# CYAN_AMP_2.net
KiCad netlist of a schematic drawn in Altium Designer
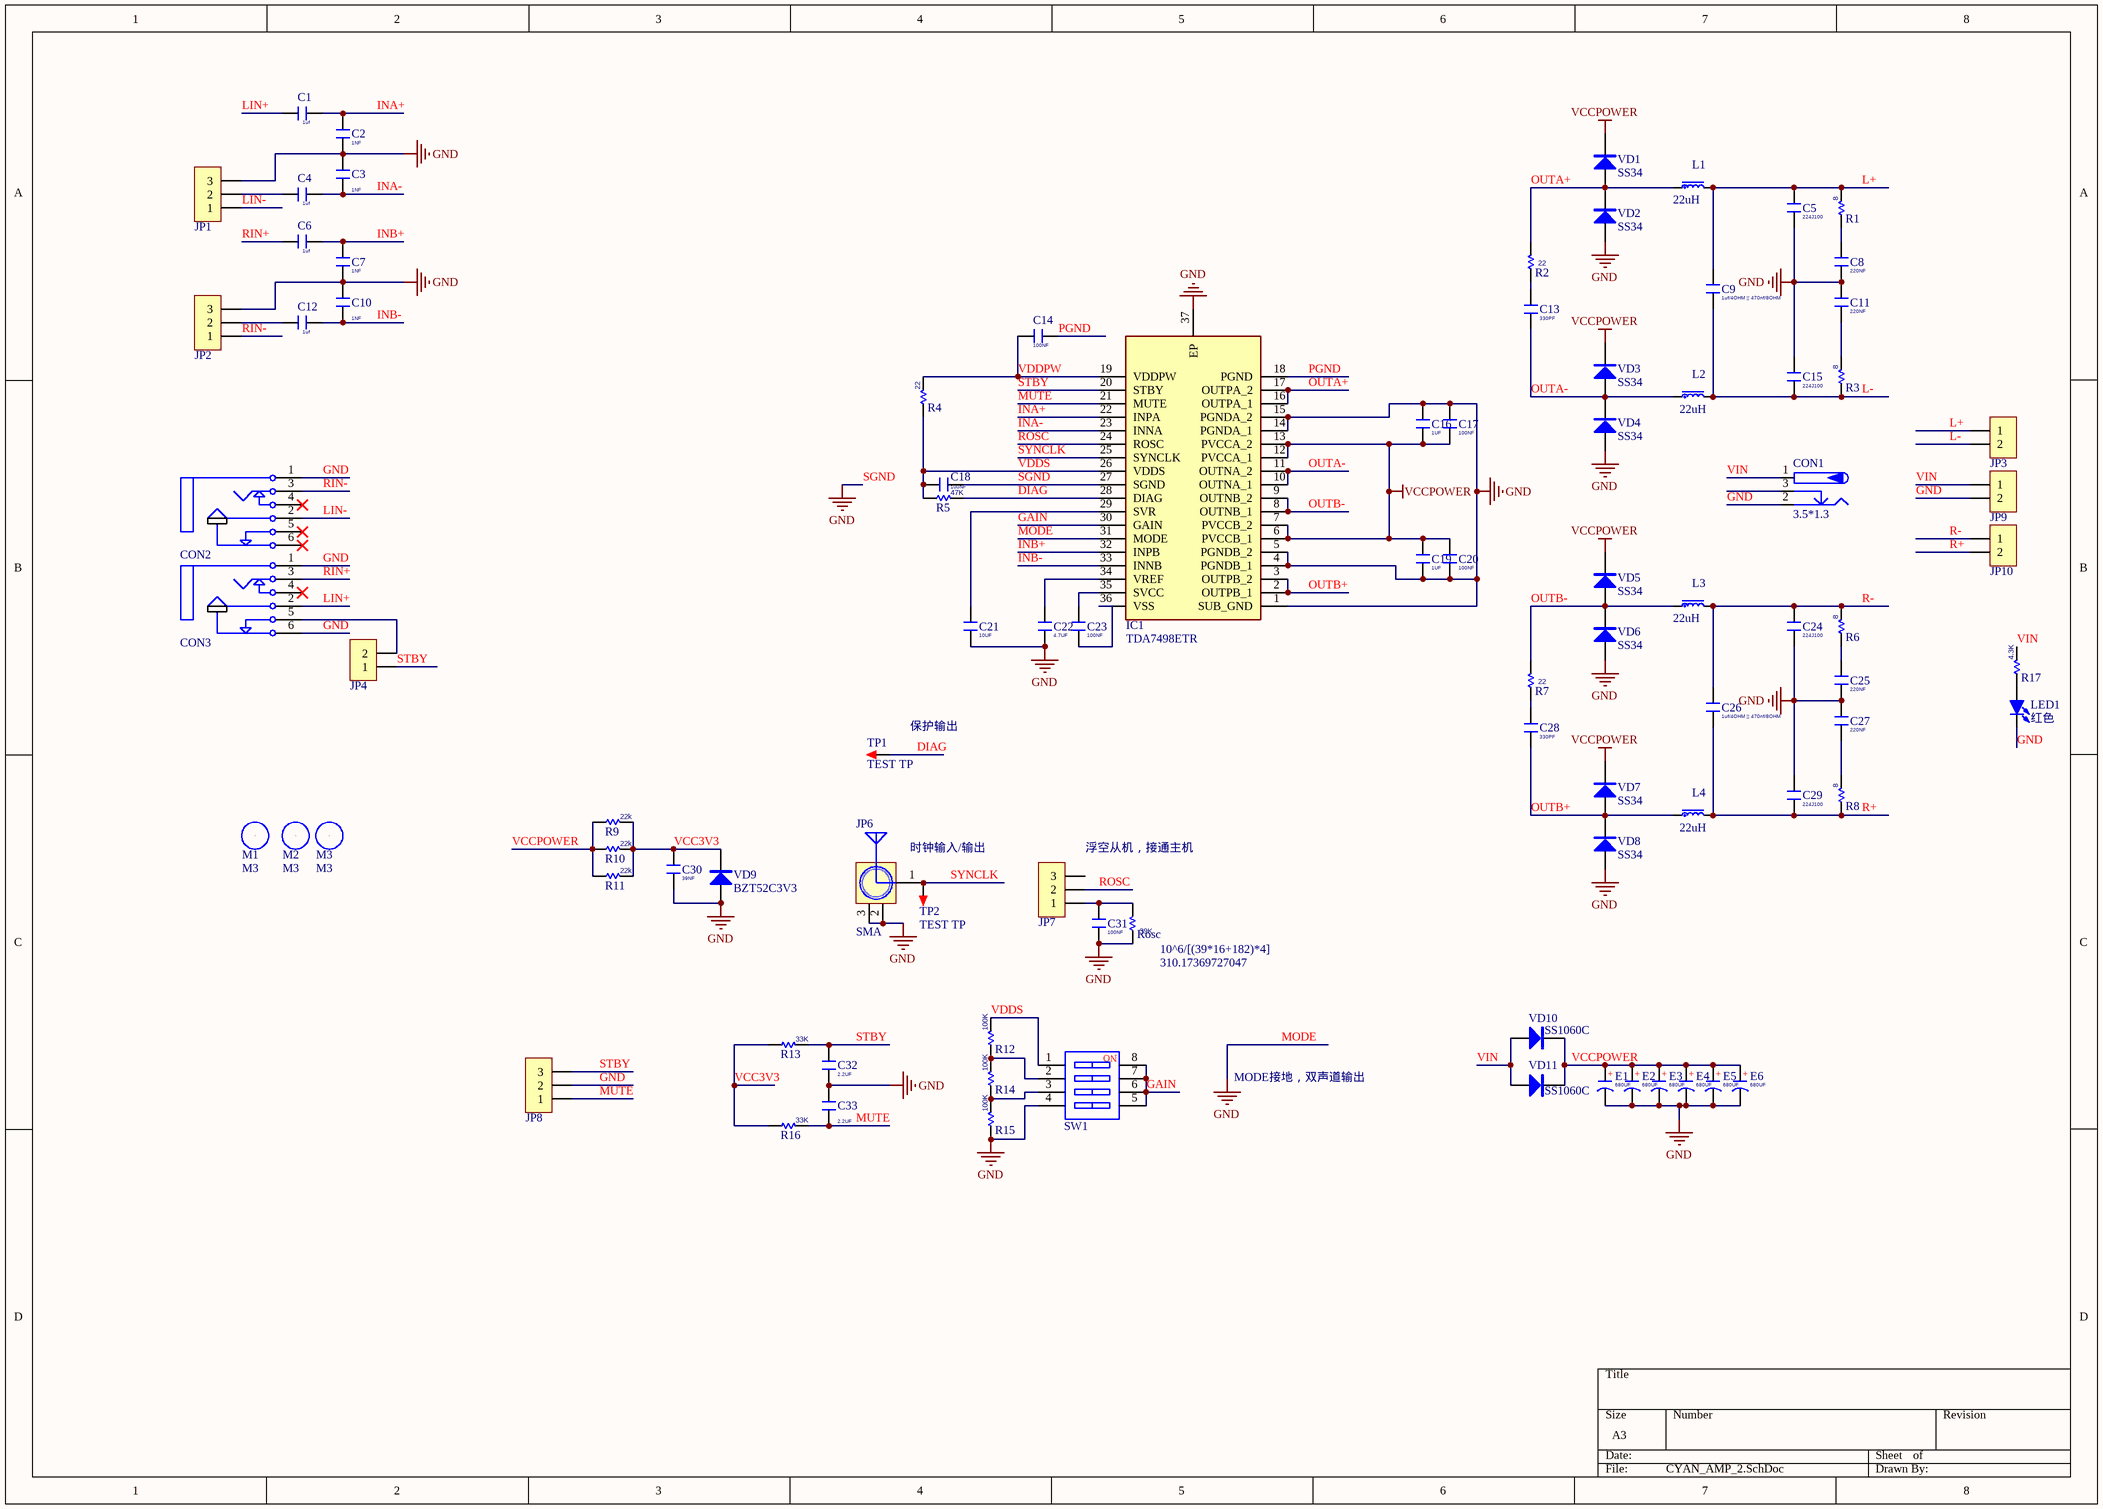
[diagram p0: CYAN_AMP_2.SchDoc]

(export (version "E")
  (design (tool "Eeschema 10.0.6"))
  (components
    (comp (ref "C1")
      (value "1uf")
      (footprint "CBB-T 5*10*5.4")
      (description "CBB电容")
      (fields (field (name "VOLTAGE") "10v"))
      (libsource (lib "电阻-电容-电感") (part "C-CBB"))
    )
    (comp (ref "C2")
      (value "1NF")
      (footprint "C 0805")
      (description "无极性贴片电容")
      (fields (field (name "VOLTAGE") "20V") (field (name "Comment") "C"))
      (libsource (lib "电阻-电容-电感") (part "C"))
    )
    (comp (ref "C3")
      (value "1NF")
      (footprint "C 0805")
      (description "无极性贴片电容")
      (fields (field (name "VOLTAGE") "20V") (field (name "Comment") "C"))
      (libsource (lib "电阻-电容-电感") (part "C"))
    )
    (comp (ref "C4")
      (value "1uf")
      (footprint "CBB-T 5*10*5.4")
      (description "CBB电容")
      (fields (field (name "VOLTAGE") "10v"))
      (libsource (lib "电阻-电容-电感") (part "C-CBB"))
    )
    (comp (ref "C5")
      (value "224J100")
      (footprint "CBB-T 5*7.5*3.5")
      (description "CBB电容")
      (fields (field (name "VOLTAGE") "10v"))
      (libsource (lib "电阻-电容-电感") (part "C-CBB"))
    )
    (comp (ref "C6")
      (value "1uf")
      (footprint "CBB-T 5*10*5.4")
      (description "CBB电容")
      (fields (field (name "VOLTAGE") "10v"))
      (libsource (lib "电阻-电容-电感") (part "C-CBB"))
    )
    (comp (ref "C7")
      (value "1NF")
      (footprint "C 0805")
      (description "无极性贴片电容")
      (fields (field (name "VOLTAGE") "20V") (field (name "Comment") "C"))
      (libsource (lib "电阻-电容-电感") (part "C"))
    )
    (comp (ref "C8")
      (value "220NF")
      (footprint "C 0805")
      (description "无极性贴片电容")
      (fields (field (name "VOLTAGE") "20V") (field (name "Comment") "C"))
      (libsource (lib "电阻-电容-电感") (part "C"))
    )
    (comp (ref "C9")
      (value "1uf/4OHM Ζ 470nf/8OHM")
      (footprint "CBB-T 5*10*5.4")
      (description "CBB电容")
      (fields (field (name "VOLTAGE") "10v"))
      (libsource (lib "电阻-电容-电感") (part "C-CBB"))
    )
    (comp (ref "C10")
      (value "1NF")
      (footprint "C 0805")
      (description "无极性贴片电容")
      (fields (field (name "VOLTAGE") "20V") (field (name "Comment") "C"))
      (libsource (lib "电阻-电容-电感") (part "C"))
    )
    (comp (ref "C11")
      (value "220NF")
      (footprint "C 0805")
      (description "无极性贴片电容")
      (fields (field (name "VOLTAGE") "20V") (field (name "Comment") "C"))
      (libsource (lib "电阻-电容-电感") (part "C"))
    )
    (comp (ref "C12")
      (value "1uf")
      (footprint "CBB-T 5*10*5.4")
      (description "CBB电容")
      (fields (field (name "VOLTAGE") "10v"))
      (libsource (lib "电阻-电容-电感") (part "C-CBB"))
    )
    (comp (ref "C13")
      (value "330PF")
      (footprint "C 0805")
      (description "无极性贴片电容")
      (fields (field (name "VOLTAGE") "20V") (field (name "Comment") "C"))
      (libsource (lib "电阻-电容-电感") (part "C"))
    )
    (comp (ref "C14")
      (value "100NF")
      (footprint "C 0805")
      (description "无极性贴片电容")
      (fields (field (name "VOLTAGE") "20V") (field (name "Comment") "C"))
      (libsource (lib "电阻-电容-电感") (part "C"))
    )
    (comp (ref "C15")
      (value "224J100")
      (footprint "CBB-T 5*7.5*3.5")
      (description "CBB电容")
      (fields (field (name "VOLTAGE") "10v"))
      (libsource (lib "电阻-电容-电感") (part "C-CBB"))
    )
    (comp (ref "C16")
      (value "1UF")
      (footprint "C 0805")
      (description "无极性贴片电容")
      (fields (field (name "VOLTAGE") "20V") (field (name "Comment") "C"))
      (libsource (lib "电阻-电容-电感") (part "C"))
    )
    (comp (ref "C17")
      (value "100NF")
      (footprint "C 0805")
      (description "无极性贴片电容")
      (fields (field (name "VOLTAGE") "20V") (field (name "Comment") "C"))
      (libsource (lib "电阻-电容-电感") (part "C"))
    )
    (comp (ref "C18")
      (value "100NF")
      (footprint "C 0805")
      (description "无极性贴片电容")
      (fields (field (name "VOLTAGE") "20V") (field (name "Comment") "C"))
      (libsource (lib "电阻-电容-电感") (part "C"))
    )
    (comp (ref "C19")
      (value "1UF")
      (footprint "C 0805")
      (description "无极性贴片电容")
      (fields (field (name "VOLTAGE") "20V") (field (name "Comment") "C"))
      (libsource (lib "电阻-电容-电感") (part "C"))
    )
    (comp (ref "C20")
      (value "100NF")
      (footprint "C 0805")
      (description "无极性贴片电容")
      (fields (field (name "VOLTAGE") "20V") (field (name "Comment") "C"))
      (libsource (lib "电阻-电容-电感") (part "C"))
    )
    (comp (ref "C21")
      (value "10UF")
      (footprint "C 0805")
      (description "无极性贴片电容")
      (fields (field (name "VOLTAGE") "20V") (field (name "Comment") "C"))
      (libsource (lib "电阻-电容-电感") (part "C"))
    )
    (comp (ref "C22")
      (value "4.7UF")
      (footprint "C 0805")
      (description "无极性贴片电容")
      (fields (field (name "VOLTAGE") "20V") (field (name "Comment") "C"))
      (libsource (lib "电阻-电容-电感") (part "C"))
    )
    (comp (ref "C23")
      (value "100NF")
      (footprint "C 0805")
      (description "无极性贴片电容")
      (fields (field (name "VOLTAGE") "20V") (field (name "Comment") "C"))
      (libsource (lib "电阻-电容-电感") (part "C"))
    )
    (comp (ref "C24")
      (value "224J100")
      (footprint "CBB-T 5*7.5*3.5")
      (description "CBB电容")
      (fields (field (name "VOLTAGE") "10v"))
      (libsource (lib "电阻-电容-电感") (part "C-CBB"))
    )
    (comp (ref "C25")
      (value "220NF")
      (footprint "C 0805")
      (description "无极性贴片电容")
      (fields (field (name "VOLTAGE") "20V") (field (name "Comment") "C"))
      (libsource (lib "电阻-电容-电感") (part "C"))
    )
    (comp (ref "C26")
      (value "1uf/4OHM Ζ 470nf/8OHM")
      (footprint "CBB-T 5*10*5.4")
      (description "CBB电容")
      (fields (field (name "VOLTAGE") "10v"))
      (libsource (lib "电阻-电容-电感") (part "C-CBB"))
    )
    (comp (ref "C27")
      (value "220NF")
      (footprint "C 0805")
      (description "无极性贴片电容")
      (fields (field (name "VOLTAGE") "20V") (field (name "Comment") "C"))
      (libsource (lib "电阻-电容-电感") (part "C"))
    )
    (comp (ref "C28")
      (value "330PF")
      (footprint "C 0805")
      (description "无极性贴片电容")
      (fields (field (name "VOLTAGE") "20V") (field (name "Comment") "C"))
      (libsource (lib "电阻-电容-电感") (part "C"))
    )
    (comp (ref "C29")
      (value "224J100")
      (footprint "CBB-T 5*7.5*3.5")
      (description "CBB电容")
      (fields (field (name "VOLTAGE") "10v"))
      (libsource (lib "电阻-电容-电感") (part "C-CBB"))
    )
    (comp (ref "C30")
      (value "39NF")
      (footprint "C 0805")
      (description "无极性贴片电容")
      (fields (field (name "VOLTAGE") "20V") (field (name "Comment") "C"))
      (libsource (lib "电阻-电容-电感") (part "C"))
    )
    (comp (ref "C31")
      (value "100NF")
      (footprint "C 0805")
      (description "无极性贴片电容")
      (fields (field (name "VOLTAGE") "20V") (field (name "Comment") "C"))
      (libsource (lib "电阻-电容-电感") (part "C"))
    )
    (comp (ref "C32")
      (value "2.2UF")
      (footprint "C 0805")
      (description "无极性贴片电容")
      (fields (field (name "VOLTAGE") "20V") (field (name "Comment") "C"))
      (libsource (lib "电阻-电容-电感") (part "C"))
    )
    (comp (ref "C33")
      (value "2.2UF")
      (footprint "C 0805")
      (description "无极性贴片电容")
      (fields (field (name "VOLTAGE") "20V") (field (name "Comment") "C"))
      (libsource (lib "电阻-电容-电感") (part "C"))
    )
    (comp (ref "CON1")
      (value "3.5*1.3")
      (footprint "DC-005")
      (description "低压电源接口")
      (libsource (lib "接口类") (part "P-DC"))
    )
    (comp (ref "CON2")
      (value "PJ342")
      (footprint "PJ343")
      (description "3.5耳机插座,6Pin")
      (libsource (lib "接口类") (part "PJ343"))
    )
    (comp (ref "CON3")
      (value "PJ342")
      (footprint "PJ343")
      (description "3.5耳机插座,6Pin")
      (libsource (lib "接口类") (part "PJ343"))
    )
    (comp (ref "E1")
      (value "680UF")
      (footprint "CAP 5.0*12.5*20-H")
      (description "直插电解电容")
      (fields (field (name "VOLTAGE") "50V"))
      (libsource (lib "电阻-电容-电感") (part "C-CAP"))
    )
    (comp (ref "E2")
      (value "680UF")
      (footprint "CAP 5.0*12.5*20-H")
      (description "直插电解电容")
      (fields (field (name "VOLTAGE") "50V"))
      (libsource (lib "电阻-电容-电感") (part "C-CAP"))
    )
    (comp (ref "E3")
      (value "680UF")
      (footprint "CAP 5.0*12.5*20-H")
      (description "直插电解电容")
      (fields (field (name "VOLTAGE") "50V"))
      (libsource (lib "电阻-电容-电感") (part "C-CAP"))
    )
    (comp (ref "E4")
      (value "680UF")
      (footprint "CAP 5.0*12.5*20-H")
      (description "直插电解电容")
      (fields (field (name "VOLTAGE") "50V"))
      (libsource (lib "电阻-电容-电感") (part "C-CAP"))
    )
    (comp (ref "E5")
      (value "680UF")
      (footprint "CAP 5.0*12.5*20-H")
      (description "直插电解电容")
      (fields (field (name "VOLTAGE") "50V"))
      (libsource (lib "电阻-电容-电感") (part "C-CAP"))
    )
    (comp (ref "E6")
      (value "680UF")
      (footprint "CAP 5.0*12.5*20-H")
      (description "直插电解电容")
      (fields (field (name "VOLTAGE") "50V"))
      (libsource (lib "电阻-电容-电感") (part "C-CAP"))
    )
    (comp (ref "IC1")
      (value "TDA7498ETR")
      (footprint "TDA7498E-SSOP36")
      (description "Integrated Circuit")
      (fields (field (name "MOUSER PART NUMBER") "511-TDA7498ETR"))
      (libsource (lib "SCHLIB") (part "TDA7498ETR"))
    )
    (comp (ref "JP1")
      (value "HDR-1X3")
      (footprint "HDR-1X3")
      (description "3P接插件")
      (libsource (lib "接插件") (part "Header 3"))
    )
    (comp (ref "JP2")
      (value "HDR-1X3")
      (footprint "HDR-1X3")
      (description "3P接插件")
      (libsource (lib "接插件") (part "Header 3"))
    )
    (comp (ref "JP3")
      (value "HDR-1X2")
      (footprint "KF301-2P")
      (description "2P接插件")
      (libsource (lib "接插件") (part "Header 2"))
    )
    (comp (ref "JP4")
      (value "HDR-1X2")
      (footprint "HDR-1X2")
      (description "2P接插件")
      (libsource (lib "") (part "Header 2_1"))
    )
    (comp (ref "JP6")
      (value "SMA")
      (footprint "SMA_FR")
      (description "SMA-2.4G射频天线接口")
      (libsource (lib "接口类") (part "SMA"))
    )
    (comp (ref "JP7")
      (value "HDR-1X3")
      (footprint "HDR-1X3")
      (description "3P接插件")
      (libsource (lib "接插件") (part "Header 3"))
    )
    (comp (ref "JP8")
      (value "HDR-1X3")
      (footprint "HDR-1X3")
      (description "3P接插件")
      (libsource (lib "接插件") (part "Header 3"))
    )
    (comp (ref "JP9")
      (value "HDR-1X2")
      (footprint "KF301-2P")
      (description "2P接插件")
      (libsource (lib "接插件") (part "Header 2"))
    )
    (comp (ref "JP10")
      (value "HDR-1X2")
      (footprint "KF301-2P")
      (description "2P接插件")
      (libsource (lib "接插件") (part "Header 2"))
    )
    (comp (ref "L1")
      (value "22uH")
      (footprint "7G17A/C")
      (description "工字电感")
      (libsource (lib "电阻-电容-电感") (part "L-PK"))
    )
    (comp (ref "L2")
      (value "22uH")
      (footprint "7G17A/C")
      (description "工字电感")
      (libsource (lib "电阻-电容-电感") (part "L-PK"))
    )
    (comp (ref "L3")
      (value "22uH")
      (footprint "7G17A/C")
      (description "工字电感")
      (libsource (lib "电阻-电容-电感") (part "L-PK"))
    )
    (comp (ref "L4")
      (value "22uH")
      (footprint "7G17A/C")
      (description "工字电感")
      (libsource (lib "电阻-电容-电感") (part "L-PK"))
    )
    (comp (ref "LED1")
      (value "红色")
      (footprint "LED 1206R")
      (description "贴片LED")
      (libsource (lib "LED") (part "LED-SMD"))
    )
    (comp (ref "M1")
      (value "M3")
      (footprint "M3 125X200")
      (description "铜柱孔")
      (libsource (lib "未分类器件") (part "M3"))
    )
    (comp (ref "M2")
      (value "M3")
      (footprint "M3 125X200")
      (description "铜柱孔")
      (libsource (lib "未分类器件") (part "M3"))
    )
    (comp (ref "M3")
      (value "M3")
      (footprint "M3 125X200")
      (description "铜柱孔")
      (libsource (lib "未分类器件") (part "M3"))
    )
    (comp (ref "R1")
      (value "8")
      (footprint "R 0805")
      (description "贴片电阻")
      (fields (field (name "Comment") "R"))
      (libsource (lib "电阻-电容-电感") (part "R"))
    )
    (comp (ref "R2")
      (value "22")
      (footprint "R 0805")
      (description "贴片电阻")
      (fields (field (name "Comment") "R"))
      (libsource (lib "电阻-电容-电感") (part "R"))
    )
    (comp (ref "R3")
      (value "8")
      (footprint "R 0805")
      (description "贴片电阻")
      (fields (field (name "Comment") "R"))
      (libsource (lib "电阻-电容-电感") (part "R"))
    )
    (comp (ref "R4")
      (value "22")
      (footprint "R 0805")
      (description "贴片电阻")
      (fields (field (name "Comment") "R"))
      (libsource (lib "电阻-电容-电感") (part "R"))
    )
    (comp (ref "R5")
      (value "47K")
      (footprint "R 0805")
      (description "贴片电阻")
      (fields (field (name "Comment") "R"))
      (libsource (lib "电阻-电容-电感") (part "R"))
    )
    (comp (ref "R6")
      (value "8")
      (footprint "R 0805")
      (description "贴片电阻")
      (fields (field (name "Comment") "R"))
      (libsource (lib "电阻-电容-电感") (part "R"))
    )
    (comp (ref "R7")
      (value "22")
      (footprint "R 0805")
      (description "贴片电阻")
      (fields (field (name "Comment") "R"))
      (libsource (lib "电阻-电容-电感") (part "R"))
    )
    (comp (ref "R8")
      (value "8")
      (footprint "R 0805")
      (description "贴片电阻")
      (fields (field (name "Comment") "R"))
      (libsource (lib "电阻-电容-电感") (part "R"))
    )
    (comp (ref "R9")
      (value "22k")
      (footprint "R 0805")
      (description "贴片电阻")
      (fields (field (name "Comment") "R"))
      (libsource (lib "电阻-电容-电感") (part "R"))
    )
    (comp (ref "R10")
      (value "22k")
      (footprint "R 0805")
      (description "贴片电阻")
      (fields (field (name "Comment") "R"))
      (libsource (lib "电阻-电容-电感") (part "R"))
    )
    (comp (ref "R11")
      (value "22k")
      (footprint "R 0805")
      (description "贴片电阻")
      (fields (field (name "Comment") "R"))
      (libsource (lib "电阻-电容-电感") (part "R"))
    )
    (comp (ref "R12")
      (value "100K")
      (footprint "R 0805")
      (description "贴片电阻")
      (fields (field (name "Comment") "R"))
      (libsource (lib "电阻-电容-电感") (part "R"))
    )
    (comp (ref "R13")
      (value "33K")
      (footprint "R 0805")
      (description "贴片电阻")
      (fields (field (name "Comment") "R"))
      (libsource (lib "电阻-电容-电感") (part "R"))
    )
    (comp (ref "R14")
      (value "100K")
      (footprint "R 0805")
      (description "贴片电阻")
      (fields (field (name "Comment") "R"))
      (libsource (lib "电阻-电容-电感") (part "R"))
    )
    (comp (ref "R15")
      (value "100K")
      (footprint "R 0805")
      (description "贴片电阻")
      (fields (field (name "Comment") "R"))
      (libsource (lib "电阻-电容-电感") (part "R"))
    )
    (comp (ref "R16")
      (value "33K")
      (footprint "R 0805")
      (description "贴片电阻")
      (fields (field (name "Comment") "R"))
      (libsource (lib "电阻-电容-电感") (part "R"))
    )
    (comp (ref "R17")
      (value "4.3K")
      (footprint "R 0805")
      (description "贴片电阻")
      (fields (field (name "Comment") "R"))
      (libsource (lib "电阻-电容-电感") (part "R"))
    )
    (comp (ref "Rosc")
      (value "39K")
      (footprint "R 0805")
      (description "贴片电阻")
      (fields (field (name "Comment") "R"))
      (libsource (lib "电阻-电容-电感") (part "R"))
    )
    (comp (ref "SW1")
      (value "CSW-4P")
      (footprint "CSW1.27 SMD-4P")
      (description "4路编码开关")
      (libsource (lib "按键-开关") (part "CSW-4P"))
    )
    (comp (ref "TP1")
      (value "TEST TP")
      (footprint "TEST TP1.4_B")
      (description "测试环")
      (libsource (lib "未分类器件") (part "TEST TP"))
    )
    (comp (ref "TP2")
      (value "TEST TP")
      (footprint "TEST TP1.4_B")
      (description "测试环")
      (libsource (lib "未分类器件") (part "TEST TP"))
    )
    (comp (ref "VD1")
      (value "SS34")
      (footprint "SMA")
      (description "肖特基二极管")
      (libsource (lib "二极管-整流桥") (part "SS14"))
    )
    (comp (ref "VD2")
      (value "SS34")
      (footprint "SMA")
      (description "肖特基二极管")
      (libsource (lib "二极管-整流桥") (part "SS14"))
    )
    (comp (ref "VD3")
      (value "SS34")
      (footprint "SMA")
      (description "肖特基二极管")
      (libsource (lib "二极管-整流桥") (part "SS14"))
    )
    (comp (ref "VD4")
      (value "SS34")
      (footprint "SMA")
      (description "肖特基二极管")
      (libsource (lib "二极管-整流桥") (part "SS14"))
    )
    (comp (ref "VD5")
      (value "SS34")
      (footprint "SMA")
      (description "肖特基二极管")
      (libsource (lib "二极管-整流桥") (part "SS14"))
    )
    (comp (ref "VD6")
      (value "SS34")
      (footprint "SMA")
      (description "肖特基二极管")
      (libsource (lib "二极管-整流桥") (part "SS14"))
    )
    (comp (ref "VD7")
      (value "SS34")
      (footprint "SMA")
      (description "肖特基二极管")
      (libsource (lib "二极管-整流桥") (part "SS14"))
    )
    (comp (ref "VD8")
      (value "SS34")
      (footprint "SMA")
      (description "肖特基二极管")
      (libsource (lib "二极管-整流桥") (part "SS14"))
    )
    (comp (ref "VD9")
      (value "BZT52C3V3")
      (footprint "SOD-123")
      (description "整流二极管")
      (libsource (lib "二极管-整流桥") (part "1N4007"))
    )
    (comp (ref "VD10")
      (value "SS1060C")
      (footprint "SMC")
      (description "肖特基二极管")
      (libsource (lib "二极管-整流桥") (part "SS34"))
    )
    (comp (ref "VD11")
      (value "SS1060C")
      (footprint "SMC")
      (description "肖特基二极管")
      (libsource (lib "二极管-整流桥") (part "SS34"))
    )
  )
  (nets
    (net (code "1") (name "/DIAG") (class "Default")
      (node (ref "IC1") (pin "28") (pinfunction "DIAG_28") (pintype "passive"))
      (node (ref "R5") (pin "2") (pinfunction "2_2") (pintype "passive"))
      (node (ref "TP1") (pin "1") (pinfunction "1_1") (pintype "passive"))
    )
    (net (code "2") (name "/GAIN") (class "Default")
      (node (ref "IC1") (pin "30") (pinfunction "GAIN_30") (pintype "passive"))
      (node (ref "SW1") (pin "5") (pinfunction "5_5") (pintype "passive"))
      (node (ref "SW1") (pin "6") (pinfunction "6_6") (pintype "passive"))
      (node (ref "SW1") (pin "7") (pinfunction "7_7") (pintype "passive"))
      (node (ref "SW1") (pin "8") (pinfunction "8_8") (pintype "passive"))
    )
    (net (code "3") (name "/INA+") (class "Default")
      (node (ref "C1") (pin "2") (pinfunction "2_2") (pintype "passive"))
      (node (ref "C2") (pin "2") (pinfunction "2_2") (pintype "passive"))
      (node (ref "IC1") (pin "22") (pinfunction "INPA_22") (pintype "passive"))
    )
    (net (code "4") (name "/INA-") (class "Default")
      (node (ref "C3") (pin "1") (pinfunction "1_1") (pintype "passive"))
      (node (ref "C4") (pin "2") (pinfunction "2_2") (pintype "passive"))
      (node (ref "IC1") (pin "23") (pinfunction "INNA_23") (pintype "passive"))
    )
    (net (code "5") (name "/INB+") (class "Default")
      (node (ref "C6") (pin "2") (pinfunction "2_2") (pintype "passive"))
      (node (ref "C7") (pin "2") (pinfunction "2_2") (pintype "passive"))
      (node (ref "IC1") (pin "32") (pinfunction "INPB_32") (pintype "passive"))
    )
    (net (code "6") (name "/INB-") (class "Default")
      (node (ref "C10") (pin "1") (pinfunction "1_1") (pintype "passive"))
      (node (ref "C12") (pin "2") (pinfunction "2_2") (pintype "passive"))
      (node (ref "IC1") (pin "33") (pinfunction "INNB_33") (pintype "passive"))
    )
    (net (code "7") (name "/L+") (class "Default")
      (node (ref "C5") (pin "2") (pinfunction "2_2") (pintype "passive"))
      (node (ref "C9") (pin "2") (pinfunction "2_2") (pintype "passive"))
      (node (ref "JP3") (pin "1") (pinfunction "1_1") (pintype "passive"))
      (node (ref "L1") (pin "2") (pinfunction "2_2") (pintype "passive"))
      (node (ref "R1") (pin "2") (pinfunction "2_2") (pintype "passive"))
    )
    (net (code "8") (name "/L-") (class "Default")
      (node (ref "C15") (pin "1") (pinfunction "1_1") (pintype "passive"))
      (node (ref "C9") (pin "1") (pinfunction "1_1") (pintype "passive"))
      (node (ref "JP3") (pin "2") (pinfunction "2_2") (pintype "passive"))
      (node (ref "L2") (pin "2") (pinfunction "2_2") (pintype "passive"))
      (node (ref "R3") (pin "1") (pinfunction "1_1") (pintype "passive"))
    )
    (net (code "9") (name "/LIN+") (class "Default")
      (node (ref "C1") (pin "1") (pinfunction "1_1") (pintype "passive"))
      (node (ref "CON3") (pin "2") (pinfunction "2_2") (pintype "passive"))
    )
    (net (code "10") (name "/LIN-") (class "Default")
      (node (ref "CON2") (pin "2") (pinfunction "2_2") (pintype "passive"))
      (node (ref "JP1") (pin "1") (pinfunction "1_1") (pintype "passive"))
    )
    (net (code "11") (name "/MUTE") (class "Default")
      (node (ref "C33") (pin "1") (pinfunction "1_1") (pintype "passive"))
      (node (ref "IC1") (pin "21") (pinfunction "MUTE_21") (pintype "passive"))
      (node (ref "JP8") (pin "1") (pinfunction "1_1") (pintype "passive"))
      (node (ref "R16") (pin "2") (pinfunction "2_2") (pintype "passive"))
    )
    (net (code "12") (name "/OUTA+") (class "Default")
      (node (ref "IC1") (pin "16") (pinfunction "OUTPA_1_16") (pintype "passive"))
      (node (ref "IC1") (pin "17") (pinfunction "OUTPA_2_17") (pintype "passive"))
      (node (ref "L1") (pin "1") (pinfunction "1_1") (pintype "passive"))
      (node (ref "R2") (pin "2") (pinfunction "2_2") (pintype "passive"))
      (node (ref "VD1") (pin "1") (pinfunction "A_1") (pintype "passive"))
      (node (ref "VD2") (pin "2") (pinfunction "K_2") (pintype "passive"))
    )
    (net (code "13") (name "/OUTA-") (class "Default")
      (node (ref "C13") (pin "1") (pinfunction "1_1") (pintype "passive"))
      (node (ref "IC1") (pin "10") (pinfunction "OUTNA_1_10") (pintype "passive"))
      (node (ref "IC1") (pin "11") (pinfunction "OUTNA_2_11") (pintype "passive"))
      (node (ref "L2") (pin "1") (pinfunction "1_1") (pintype "passive"))
      (node (ref "VD3") (pin "1") (pinfunction "A_1") (pintype "passive"))
      (node (ref "VD4") (pin "2") (pinfunction "K_2") (pintype "passive"))
    )
    (net (code "14") (name "/OUTB+") (class "Default")
      (node (ref "C28") (pin "1") (pinfunction "1_1") (pintype "passive"))
      (node (ref "IC1") (pin "2") (pinfunction "OUTPB_1_2") (pintype "passive"))
      (node (ref "IC1") (pin "3") (pinfunction "OUTPB_2_3") (pintype "passive"))
      (node (ref "L4") (pin "1") (pinfunction "1_1") (pintype "passive"))
      (node (ref "VD7") (pin "1") (pinfunction "A_1") (pintype "passive"))
      (node (ref "VD8") (pin "2") (pinfunction "K_2") (pintype "passive"))
    )
    (net (code "15") (name "/OUTB-") (class "Default")
      (node (ref "IC1") (pin "8") (pinfunction "OUTNB_1_8") (pintype "passive"))
      (node (ref "IC1") (pin "9") (pinfunction "OUTNB_2_9") (pintype "passive"))
      (node (ref "L3") (pin "1") (pinfunction "1_1") (pintype "passive"))
      (node (ref "R7") (pin "2") (pinfunction "2_2") (pintype "passive"))
      (node (ref "VD5") (pin "1") (pinfunction "A_1") (pintype "passive"))
      (node (ref "VD6") (pin "2") (pinfunction "K_2") (pintype "passive"))
    )
    (net (code "16") (name "/PGND") (class "Default")
      (node (ref "C14") (pin "1") (pinfunction "1_1") (pintype "passive"))
      (node (ref "IC1") (pin "18") (pinfunction "PGND_18") (pintype "passive"))
    )
    (net (code "17") (name "/R+") (class "Default")
      (node (ref "C26") (pin "1") (pinfunction "1_1") (pintype "passive"))
      (node (ref "C29") (pin "1") (pinfunction "1_1") (pintype "passive"))
      (node (ref "JP10") (pin "2") (pinfunction "2_2") (pintype "passive"))
      (node (ref "L4") (pin "2") (pinfunction "2_2") (pintype "passive"))
      (node (ref "R8") (pin "1") (pinfunction "1_1") (pintype "passive"))
    )
    (net (code "18") (name "/R-") (class "Default")
      (node (ref "C24") (pin "2") (pinfunction "2_2") (pintype "passive"))
      (node (ref "C26") (pin "2") (pinfunction "2_2") (pintype "passive"))
      (node (ref "JP10") (pin "1") (pinfunction "1_1") (pintype "passive"))
      (node (ref "L3") (pin "2") (pinfunction "2_2") (pintype "passive"))
      (node (ref "R6") (pin "2") (pinfunction "2_2") (pintype "passive"))
    )
    (net (code "19") (name "/RIN+") (class "Default")
      (node (ref "C6") (pin "1") (pinfunction "1_1") (pintype "passive"))
      (node (ref "CON3") (pin "3") (pinfunction "3_3") (pintype "passive"))
    )
    (net (code "20") (name "/RIN-") (class "Default")
      (node (ref "CON2") (pin "3") (pinfunction "3_3") (pintype "passive"))
      (node (ref "JP2") (pin "1") (pinfunction "1_1") (pintype "passive"))
    )
    (net (code "21") (name "/ROSC") (class "Default")
      (node (ref "IC1") (pin "24") (pinfunction "ROSC_24") (pintype "passive"))
      (node (ref "JP7") (pin "2") (pinfunction "2_2") (pintype "passive"))
    )
    (net (code "22") (name "/STBY") (class "Default")
      (node (ref "C32") (pin "2") (pinfunction "2_2") (pintype "passive"))
      (node (ref "IC1") (pin "20") (pinfunction "STBY_20") (pintype "passive"))
      (node (ref "JP4") (pin "1") (pinfunction "1_1") (pintype "passive"))
      (node (ref "JP8") (pin "3") (pinfunction "3_3") (pintype "passive"))
      (node (ref "R13") (pin "2") (pinfunction "2_2") (pintype "passive"))
    )
    (net (code "23") (name "/SYNCLK") (class "Default")
      (node (ref "IC1") (pin "25") (pinfunction "SYNCLK_25") (pintype "passive"))
      (node (ref "JP6") (pin "1") (pinfunction "ANT_1") (pintype "passive"))
      (node (ref "TP2") (pin "1") (pinfunction "1_1") (pintype "passive"))
    )
    (net (code "24") (name "/VCC3V3") (class "Default")
      (node (ref "C30") (pin "2") (pinfunction "2_2") (pintype "passive"))
      (node (ref "R10") (pin "2") (pinfunction "2_2") (pintype "passive"))
      (node (ref "R11") (pin "2") (pinfunction "2_2") (pintype "passive"))
      (node (ref "R13") (pin "1") (pinfunction "1_1") (pintype "passive"))
      (node (ref "R16") (pin "1") (pinfunction "1_1") (pintype "passive"))
      (node (ref "R9") (pin "2") (pinfunction "2_2") (pintype "passive"))
      (node (ref "VD9") (pin "2") (pinfunction "K_2") (pintype "passive"))
    )
    (net (code "25") (name "/VDDPW") (class "Default")
      (node (ref "C14") (pin "2") (pinfunction "2_2") (pintype "passive"))
      (node (ref "IC1") (pin "19") (pinfunction "VDDPW_19") (pintype "passive"))
      (node (ref "R4") (pin "2") (pinfunction "2_2") (pintype "passive"))
    )
    (net (code "26") (name "/VDDS") (class "Default")
      (node (ref "C18") (pin "2") (pinfunction "2_2") (pintype "passive"))
      (node (ref "IC1") (pin "26") (pinfunction "VDDS_26") (pintype "passive"))
      (node (ref "R12") (pin "2") (pinfunction "2_2") (pintype "passive"))
      (node (ref "R4") (pin "1") (pinfunction "1_1") (pintype "passive"))
      (node (ref "R5") (pin "1") (pinfunction "1_1") (pintype "passive"))
      (node (ref "SW1") (pin "1") (pinfunction "1_1") (pintype "passive"))
    )
    (net (code "27") (name "/VIN") (class "Default")
      (node (ref "CON1") (pin "1") (pintype "power_in"))
      (node (ref "JP9") (pin "1") (pinfunction "1_1") (pintype "passive"))
      (node (ref "R17") (pin "2") (pinfunction "2_2") (pintype "passive"))
      (node (ref "VD10") (pin "1") (pinfunction "A_1") (pintype "passive"))
      (node (ref "VD11") (pin "1") (pinfunction "A_1") (pintype "passive"))
    )
    (net (code "28") (name "GND") (class "Default")
      (node (ref "C10") (pin "2") (pinfunction "2_2") (pintype "passive"))
      (node (ref "C11") (pin "2") (pinfunction "2_2") (pintype "passive"))
      (node (ref "C15") (pin "2") (pinfunction "2_2") (pintype "passive"))
      (node (ref "C16") (pin "2") (pinfunction "2_2") (pintype "passive"))
      (node (ref "C17") (pin "2") (pinfunction "2_2") (pintype "passive"))
      (node (ref "C18") (pin "1") (pinfunction "1_1") (pintype "passive"))
      (node (ref "C19") (pin "2") (pinfunction "2_2") (pintype "passive"))
      (node (ref "C2") (pin "1") (pinfunction "1_1") (pintype "passive"))
      (node (ref "C20") (pin "2") (pinfunction "2_2") (pintype "passive"))
      (node (ref "C21") (pin "1") (pinfunction "1_1") (pintype "passive"))
      (node (ref "C22") (pin "1") (pinfunction "1_1") (pintype "passive"))
      (node (ref "C24") (pin "1") (pinfunction "1_1") (pintype "passive"))
      (node (ref "C25") (pin "1") (pinfunction "1_1") (pintype "passive"))
      (node (ref "C27") (pin "2") (pinfunction "2_2") (pintype "passive"))
      (node (ref "C29") (pin "2") (pinfunction "2_2") (pintype "passive"))
      (node (ref "C3") (pin "2") (pinfunction "2_2") (pintype "passive"))
      (node (ref "C30") (pin "1") (pinfunction "1_1") (pintype "passive"))
      (node (ref "C31") (pin "1") (pinfunction "1_1") (pintype "passive"))
      (node (ref "C32") (pin "1") (pinfunction "1_1") (pintype "passive"))
      (node (ref "C33") (pin "2") (pinfunction "2_2") (pintype "passive"))
      (node (ref "C5") (pin "1") (pinfunction "1_1") (pintype "passive"))
      (node (ref "C7") (pin "1") (pinfunction "1_1") (pintype "passive"))
      (node (ref "C8") (pin "1") (pinfunction "1_1") (pintype "passive"))
      (node (ref "CON1") (pin "2") (pintype "power_in"))
      (node (ref "CON2") (pin "1") (pinfunction "1_1") (pintype "passive"))
      (node (ref "CON3") (pin "1") (pinfunction "1_1") (pintype "passive"))
      (node (ref "CON3") (pin "6") (pinfunction "6_6") (pintype "passive"))
      (node (ref "E1") (pin "2") (pinfunction "2_2") (pintype "passive"))
      (node (ref "E2") (pin "2") (pinfunction "2_2") (pintype "passive"))
      (node (ref "E3") (pin "2") (pinfunction "2_2") (pintype "passive"))
      (node (ref "E4") (pin "2") (pinfunction "2_2") (pintype "passive"))
      (node (ref "E5") (pin "2") (pinfunction "2_2") (pintype "passive"))
      (node (ref "E6") (pin "2") (pinfunction "2_2") (pintype "passive"))
      (node (ref "IC1") (pin "1") (pinfunction "SUB_GND_1") (pintype "passive"))
      (node (ref "IC1") (pin "14") (pinfunction "PGNDA_1_14") (pintype "passive"))
      (node (ref "IC1") (pin "15") (pinfunction "PGNDA_2_15") (pintype "passive"))
      (node (ref "IC1") (pin "27") (pinfunction "SGND_27") (pintype "passive"))
      (node (ref "IC1") (pin "31") (pinfunction "MODE_31") (pintype "passive"))
      (node (ref "IC1") (pin "37") (pinfunction "EP_37") (pintype "passive"))
      (node (ref "IC1") (pin "4") (pinfunction "PGNDB_1_4") (pintype "passive"))
      (node (ref "IC1") (pin "5") (pinfunction "PGNDB_2_5") (pintype "passive"))
      (node (ref "JP1") (pin "3") (pinfunction "3_3") (pintype "passive"))
      (node (ref "JP2") (pin "3") (pinfunction "3_3") (pintype "passive"))
      (node (ref "JP6") (pin "2") (pinfunction "GND_2") (pintype "passive"))
      (node (ref "JP6") (pin "3") (pinfunction "GND_3") (pintype "passive"))
      (node (ref "JP8") (pin "2") (pinfunction "2_2") (pintype "passive"))
      (node (ref "JP9") (pin "2") (pinfunction "2_2") (pintype "passive"))
      (node (ref "LED1") (pin "2") (pinfunction "K_2") (pintype "passive"))
      (node (ref "R15") (pin "1") (pinfunction "1_1") (pintype "passive"))
      (node (ref "Rosc") (pin "1") (pinfunction "1_1") (pintype "passive"))
      (node (ref "SW1") (pin "4") (pinfunction "4_4") (pintype "passive"))
      (node (ref "VD2") (pin "1") (pinfunction "A_1") (pintype "passive"))
      (node (ref "VD4") (pin "1") (pinfunction "A_1") (pintype "passive"))
      (node (ref "VD6") (pin "1") (pinfunction "A_1") (pintype "passive"))
      (node (ref "VD8") (pin "1") (pinfunction "A_1") (pintype "passive"))
      (node (ref "VD9") (pin "1") (pinfunction "A_1") (pintype "passive"))
    )
    (net (code "29") (name "Net-(C4-Pad1)") (class "Default")
      (node (ref "C4") (pin "1") (pinfunction "1_1") (pintype "passive"))
      (node (ref "JP1") (pin "2") (pinfunction "2_2") (pintype "passive"))
    )
    (net (code "30") (name "Net-(C8-Pad2)") (class "Default")
      (node (ref "C8") (pin "2") (pinfunction "2_2") (pintype "passive"))
      (node (ref "R1") (pin "1") (pinfunction "1_1") (pintype "passive"))
    )
    (net (code "31") (name "Net-(C11-Pad1)") (class "Default")
      (node (ref "C11") (pin "1") (pinfunction "1_1") (pintype "passive"))
      (node (ref "R3") (pin "2") (pinfunction "2_2") (pintype "passive"))
    )
    (net (code "32") (name "Net-(C12-Pad1)") (class "Default")
      (node (ref "C12") (pin "1") (pinfunction "1_1") (pintype "passive"))
      (node (ref "JP2") (pin "2") (pinfunction "2_2") (pintype "passive"))
    )
    (net (code "33") (name "Net-(C13-Pad2)") (class "Default")
      (node (ref "C13") (pin "2") (pinfunction "2_2") (pintype "passive"))
      (node (ref "R2") (pin "1") (pinfunction "1_1") (pintype "passive"))
    )
    (net (code "34") (name "Net-(C25-Pad2)") (class "Default")
      (node (ref "C25") (pin "2") (pinfunction "2_2") (pintype "passive"))
      (node (ref "R6") (pin "1") (pinfunction "1_1") (pintype "passive"))
    )
    (net (code "35") (name "Net-(C27-Pad1)") (class "Default")
      (node (ref "C27") (pin "1") (pinfunction "1_1") (pintype "passive"))
      (node (ref "R8") (pin "2") (pinfunction "2_2") (pintype "passive"))
    )
    (net (code "36") (name "Net-(C28-Pad2)") (class "Default")
      (node (ref "C28") (pin "2") (pinfunction "2_2") (pintype "passive"))
      (node (ref "R7") (pin "1") (pinfunction "1_1") (pintype "passive"))
    )
    (net (code "37") (name "Net-(C31-Pad2)") (class "Default")
      (node (ref "C31") (pin "2") (pinfunction "2_2") (pintype "passive"))
      (node (ref "JP7") (pin "1") (pinfunction "1_1") (pintype "passive"))
      (node (ref "Rosc") (pin "2") (pinfunction "2_2") (pintype "passive"))
    )
    (net (code "38") (name "Net-(CON3-Pad5)") (class "Default")
      (node (ref "CON3") (pin "5") (pinfunction "5_5") (pintype "passive"))
      (node (ref "JP4") (pin "2") (pinfunction "2_2") (pintype "passive"))
    )
    (net (code "39") (name "Net-(IC1-SVCC)") (class "Default")
      (node (ref "C23") (pin "2") (pinfunction "2_2") (pintype "passive"))
      (node (ref "IC1") (pin "35") (pinfunction "SVCC_35") (pintype "passive"))
    )
    (net (code "40") (name "Net-(IC1-SVR)") (class "Default")
      (node (ref "C21") (pin "2") (pinfunction "2_2") (pintype "passive"))
      (node (ref "IC1") (pin "29") (pinfunction "SVR_29") (pintype "passive"))
    )
    (net (code "41") (name "Net-(IC1-VREF)") (class "Default")
      (node (ref "C22") (pin "2") (pinfunction "2_2") (pintype "passive"))
      (node (ref "IC1") (pin "34") (pinfunction "VREF_34") (pintype "passive"))
    )
    (net (code "42") (name "Net-(IC1-VSS)") (class "Default")
      (node (ref "C23") (pin "1") (pinfunction "1_1") (pintype "passive"))
      (node (ref "IC1") (pin "36") (pinfunction "VSS_36") (pintype "passive"))
    )
    (net (code "43") (name "Net-(LED1-A)") (class "Default")
      (node (ref "LED1") (pin "1") (pinfunction "A_1") (pintype "passive"))
      (node (ref "R17") (pin "1") (pinfunction "1_1") (pintype "passive"))
    )
    (net (code "44") (name "Net-(R12-Pad1)") (class "Default")
      (node (ref "R12") (pin "1") (pinfunction "1_1") (pintype "passive"))
      (node (ref "R14") (pin "2") (pinfunction "2_2") (pintype "passive"))
      (node (ref "SW1") (pin "2") (pinfunction "2_2") (pintype "passive"))
    )
    (net (code "45") (name "Net-(R14-Pad1)") (class "Default")
      (node (ref "R14") (pin "1") (pinfunction "1_1") (pintype "passive"))
      (node (ref "R15") (pin "2") (pinfunction "2_2") (pintype "passive"))
      (node (ref "SW1") (pin "3") (pinfunction "3_3") (pintype "passive"))
    )
    (net (code "46") (name "VCCPOWER") (class "Default")
      (node (ref "C16") (pin "1") (pinfunction "1_1") (pintype "passive"))
      (node (ref "C17") (pin "1") (pinfunction "1_1") (pintype "passive"))
      (node (ref "C19") (pin "1") (pinfunction "1_1") (pintype "passive"))
      (node (ref "C20") (pin "1") (pinfunction "1_1") (pintype "passive"))
      (node (ref "E1") (pin "1") (pinfunction "1_1") (pintype "passive"))
      (node (ref "E2") (pin "1") (pinfunction "1_1") (pintype "passive"))
      (node (ref "E3") (pin "1") (pinfunction "1_1") (pintype "passive"))
      (node (ref "E4") (pin "1") (pinfunction "1_1") (pintype "passive"))
      (node (ref "E5") (pin "1") (pinfunction "1_1") (pintype "passive"))
      (node (ref "E6") (pin "1") (pinfunction "1_1") (pintype "passive"))
      (node (ref "IC1") (pin "12") (pinfunction "PVCCA_1_12") (pintype "passive"))
      (node (ref "IC1") (pin "13") (pinfunction "PVCCA_2_13") (pintype "passive"))
      (node (ref "IC1") (pin "6") (pinfunction "PVCCB_1_6") (pintype "passive"))
      (node (ref "IC1") (pin "7") (pinfunction "PVCCB_2_7") (pintype "passive"))
      (node (ref "R10") (pin "1") (pinfunction "1_1") (pintype "passive"))
      (node (ref "R11") (pin "1") (pinfunction "1_1") (pintype "passive"))
      (node (ref "R9") (pin "1") (pinfunction "1_1") (pintype "passive"))
      (node (ref "VD1") (pin "2") (pinfunction "K_2") (pintype "passive"))
      (node (ref "VD10") (pin "2") (pinfunction "K_2") (pintype "passive"))
      (node (ref "VD11") (pin "2") (pinfunction "K_2") (pintype "passive"))
      (node (ref "VD3") (pin "2") (pinfunction "K_2") (pintype "passive"))
      (node (ref "VD5") (pin "2") (pinfunction "K_2") (pintype "passive"))
      (node (ref "VD7") (pin "2") (pinfunction "K_2") (pintype "passive"))
    )
    (net (code "47") (name "unconnected-(CON1-Pad3)") (class "Default")
      (node (ref "CON1") (pin "3") (pintype "power_in"))
    )
    (net (code "48") (name "unconnected-(CON2-Pad4)") (class "Default")
      (node (ref "CON2") (pin "4") (pinfunction "4_4") (pintype "passive+no_connect"))
    )
    (net (code "49") (name "unconnected-(CON2-Pad5)") (class "Default")
      (node (ref "CON2") (pin "5") (pinfunction "5_5") (pintype "passive+no_connect"))
    )
    (net (code "50") (name "unconnected-(CON2-Pad6)") (class "Default")
      (node (ref "CON2") (pin "6") (pinfunction "6_6") (pintype "passive+no_connect"))
    )
    (net (code "51") (name "unconnected-(CON3-Pad4)") (class "Default")
      (node (ref "CON3") (pin "4") (pinfunction "4_4") (pintype "passive+no_connect"))
    )
    (net (code "52") (name "unconnected-(JP7-Pad3)") (class "Default")
      (node (ref "JP7") (pin "3") (pinfunction "3_3") (pintype "passive"))
    )
    (net (code "53") (name "unconnected-(M1-Pad0)") (class "Default")
      (node (ref "M1") (pin "0") (pinfunction "0_0") (pintype "passive"))
    )
    (net (code "54") (name "unconnected-(M2-Pad0)") (class "Default")
      (node (ref "M2") (pin "0") (pinfunction "0_0") (pintype "passive"))
    )
    (net (code "55") (name "unconnected-(M3-Pad0)") (class "Default")
      (node (ref "M3") (pin "0") (pinfunction "0_0") (pintype "passive"))
    )
  )
)
